# Rail_Protection_AD.net
KiCad netlist of a schematic drawn in Altium Designer
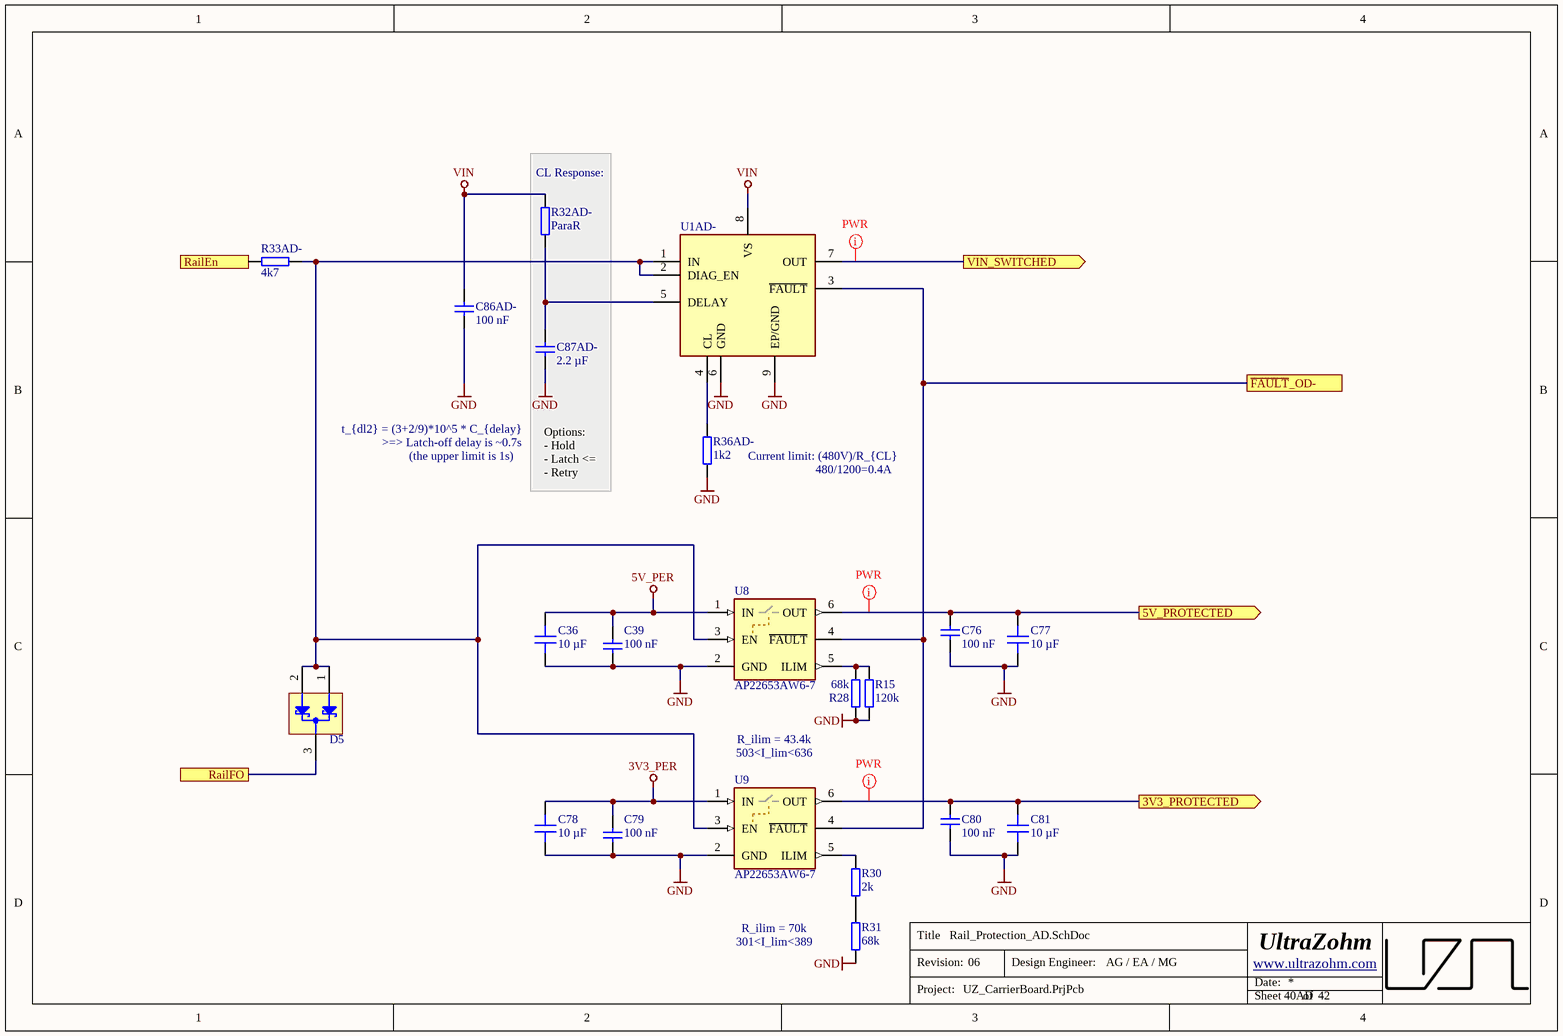
[diagram p0: Rail_Protection_AD.SchDoc]

(export (version "E")
  (design (tool "Eeschema 10.0.6"))
  (components
    (comp (ref "C36")
      (value "10 µF")
      (footprint "C_0603_TE")
      (description "Capacitor 0603, 16 VDC, 10 µF, X5R")
      (fields
        (field (name "MANUFACTURER PART NUMBER") "CL10A106MO8NQNC")
        (field (name "MANUFACTURER") "Samsung Electro-Mechanics")
        (field (name "CREATED FROM") "AGeiger")
      )
      (libsource (lib "user") (part "Capacitor"))
    )
    (comp (ref "C39")
      (value "100 nF")
      (footprint "C_0603_TE")
      (description "Generic capacitor")
      (fields
        (field (name "MANUFACTURER PART NUMBER") "UZgen_C_0603_100nF_50V_X7R")
        (field (name "MANUFACTURER") "UZgen")
        (field (name "CREATED FROM") "AGeiger")
      )
      (libsource (lib "user") (part "CAP-NP"))
    )
    (comp (ref "C76")
      (value "100 nF")
      (footprint "C_0603_TE")
      (description "Generic capacitor")
      (fields
        (field (name "MANUFACTURER PART NUMBER") "UZgen_C_0603_100nF_50V_X7R")
        (field (name "MANUFACTURER") "UZgen")
        (field (name "CREATED FROM") "AGeiger")
      )
      (libsource (lib "user") (part "CAP-NP"))
    )
    (comp (ref "C77")
      (value "10 µF")
      (footprint "C_0603_TE")
      (description "Capacitor 0603, 16 VDC, 10 µF, X5R")
      (fields
        (field (name "MANUFACTURER PART NUMBER") "CL10A106MO8NQNC")
        (field (name "MANUFACTURER") "Samsung Electro-Mechanics")
        (field (name "CREATED FROM") "AGeiger")
      )
      (libsource (lib "user") (part "Capacitor"))
    )
    (comp (ref "C78")
      (value "10 µF")
      (footprint "C_0603_TE")
      (description "Capacitor 0603, 16 VDC, 10 µF, X5R")
      (fields
        (field (name "MANUFACTURER PART NUMBER") "CL10A106MO8NQNC")
        (field (name "MANUFACTURER") "Samsung Electro-Mechanics")
        (field (name "CREATED FROM") "AGeiger")
      )
      (libsource (lib "user") (part "Capacitor"))
    )
    (comp (ref "C79")
      (value "100 nF")
      (footprint "C_0603_TE")
      (description "Generic capacitor")
      (fields
        (field (name "MANUFACTURER PART NUMBER") "UZgen_C_0603_100nF_50V_X7R")
        (field (name "MANUFACTURER") "UZgen")
        (field (name "CREATED FROM") "AGeiger")
      )
      (libsource (lib "user") (part "CAP-NP"))
    )
    (comp (ref "C80")
      (value "100 nF")
      (footprint "C_0603_TE")
      (description "Generic capacitor")
      (fields
        (field (name "MANUFACTURER PART NUMBER") "UZgen_C_0603_100nF_50V_X7R")
        (field (name "MANUFACTURER") "UZgen")
        (field (name "CREATED FROM") "AGeiger")
      )
      (libsource (lib "user") (part "CAP-NP"))
    )
    (comp (ref "C81")
      (value "10 µF")
      (footprint "C_0603_TE")
      (description "Capacitor 0603, 16 VDC, 10 µF, X5R")
      (fields
        (field (name "MANUFACTURER PART NUMBER") "CL10A106MO8NQNC")
        (field (name "MANUFACTURER") "Samsung Electro-Mechanics")
        (field (name "CREATED FROM") "AGeiger")
      )
      (libsource (lib "user") (part "Capacitor"))
    )
    (comp (ref "C86AD-")
      (value "100 nF")
      (footprint "C_0603_TE")
      (description "Generic capacitor")
      (fields
        (field (name "MANUFACTURER PART NUMBER") "UZgen_C_0603_100nF_50V_X7R")
        (field (name "MANUFACTURER") "UZgen")
        (field (name "CREATED FROM") "AGeiger")
      )
      (libsource (lib "user") (part "CAP-NP"))
    )
    (comp (ref "C87AD-")
      (value "2.2 µF")
      (footprint "C_0603_TE")
      (description "Generic capacitor")
      (fields
        (field (name "MANUFACTURER PART NUMBER") "UZgen_C_0603_2.2uF_50V_X7R")
        (field (name "MANUFACTURER") "UZgen")
        (field (name "CREATED FROM") "UZgenTool")
      )
      (libsource (lib "user") (part "CAP-NP"))
    )
    (comp (ref "D5")
      (value "BAT54CT-7-F")
      (footprint "SOT523-3")
      (description "Surface-mount Schottky Barrier Diode, 1 Pair Common Cathode 1V@100mA 200mA 2uA@25V 30V SOT-523-3")
      (fields
        (field (name "MANUFACTURER") "Diodes Incorporated")
        (field (name "LCSC PART NUMBER") "C134407")
        (field (name "CREATED FROM") "MGeier")
      )
      (libsource (lib "user") (part "DualCommonCathode3K"))
    )
    (comp (ref "R15")
      (value "120k")
      (footprint "R_0603_TE")
      (description "Generic resistor")
      (fields
        (field (name "MANUFACTURER PART NUMBER") "UZgen_R_0603_120k")
        (field (name "MANUFACTURER") "UZgen")
        (field (name "CREATED FROM") "UZgenTool")
      )
      (libsource (lib "user") (part "RES"))
    )
    (comp (ref "R28")
      (value "68k")
      (footprint "R_0603_TE")
      (description "Generic resistor")
      (fields
        (field (name "MANUFACTURER PART NUMBER") "UZgen_R_0603_68k")
        (field (name "MANUFACTURER") "UZgen")
        (field (name "CREATED FROM") "UZgenTool")
      )
      (libsource (lib "user") (part "RES"))
    )
    (comp (ref "R30")
      (value "2k")
      (footprint "R_0603_TE")
      (description "Generic resistor")
      (fields
        (field (name "MANUFACTURER PART NUMBER") "UZgen_R_0603_2k")
        (field (name "MANUFACTURER") "UZgen")
        (field (name "CREATED FROM") "UZgenTool")
      )
      (libsource (lib "user") (part "RES"))
    )
    (comp (ref "R31")
      (value "68k")
      (footprint "R_0603_TE")
      (description "Generic resistor")
      (fields
        (field (name "MANUFACTURER PART NUMBER") "UZgen_R_0603_68k")
        (field (name "MANUFACTURER") "UZgen")
        (field (name "CREATED FROM") "UZgenTool")
      )
      (libsource (lib "user") (part "RES"))
    )
    (comp (ref "R32AD-")
      (value "ParaR")
      (footprint "R_0603_TE")
      (description "Generic resistor (parametric)")
      (fields
        (field (name "MANUFACTURER PART NUMBER") "UZgen_R_0603_ParaR")
        (field (name "MANUFACTURER") "UZgen")
        (field (name "CREATED FROM") "UZgenTool")
      )
      (libsource (lib "user") (part "RES"))
    )
    (comp (ref "R33AD-")
      (value "4k7")
      (footprint "R_0603_TE")
      (description "Generic resistor")
      (fields
        (field (name "MANUFACTURER PART NUMBER") "UZgen_R_0603_4k7")
        (field (name "MANUFACTURER") "UZgen")
        (field (name "CREATED FROM") "UZgenTool")
      )
      (libsource (lib "user") (part "RES"))
    )
    (comp (ref "R36AD-")
      (value "1k2")
      (footprint "R_0603_TE")
      (description "Generic resistor")
      (fields
        (field (name "MANUFACTURER PART NUMBER") "UZgen_R_0603_1k2")
        (field (name "MANUFACTURER") "UZgen")
        (field (name "CREATED FROM") "UZgenTool")
      )
      (libsource (lib "user") (part "RES"))
    )
    (comp (ref "U1AD-")
      (value "TPS1H000AQDGNRQ1")
      (footprint "SOP65P490X110-9N")
      (fields
        (field (name "MANUFACTURER") "Texas Instruments")
        (field (name "LCSC PART NUMBER") "C2653764")
        (field (name "CREATED FROM") "FRosner")
      )
      (libsource (lib "user") (part "TPS1H000AQDGNRQ1"))
    )
    (comp (ref "U8")
      (value "AP22653AW6-7")
      (footprint "TSOT26-6")
      (description "Precision Adjustable Current-limited Power Switch")
      (fields
        (field (name "MANUFACTURER") "Diodes Incorporated")
        (field (name "LCSC PART NUMBER") "C1511768")
        (field (name "CREATED FROM") "MGeier")
      )
      (libsource (lib "user") (part "AP22653W6-7"))
    )
    (comp (ref "U9")
      (value "AP22653AW6-7")
      (footprint "TSOT26-6")
      (description "Precision Adjustable Current-limited Power Switch")
      (fields
        (field (name "MANUFACTURER") "Diodes Incorporated")
        (field (name "LCSC PART NUMBER") "C1511768")
        (field (name "CREATED FROM") "MGeier")
      )
      (libsource (lib "user") (part "AP22653W6-7"))
    )
  )
  (nets
    (net (code "1") (name "/3V3_PROTECTED") (class "Default")
      (node (ref "C80") (pin "1") (pinfunction "1_1") (pintype "passive"))
      (node (ref "C81") (pin "2") (pinfunction "2_2") (pintype "passive"))
      (node (ref "U9") (pin "6") (pinfunction "OUT_6") (pintype "output"))
    )
    (net (code "2") (name "/5V_PROTECTED") (class "Default")
      (node (ref "C76") (pin "1") (pinfunction "1_1") (pintype "passive"))
      (node (ref "C77") (pin "2") (pinfunction "2_2") (pintype "passive"))
      (node (ref "U8") (pin "6") (pinfunction "OUT_6") (pintype "output"))
    )
    (net (code "3") (name "/RailEn") (class "Default")
      (node (ref "R33AD-") (pin "1") (pinfunction "1_1") (pintype "passive"))
    )
    (net (code "4") (name "/RailFO") (class "Default")
      (node (ref "D5") (pin "3") (pinfunction "K_3") (pintype "passive"))
    )
    (net (code "5") (name "/VIN_SWITCHED") (class "Default")
      (node (ref "U1AD-") (pin "7") (pinfunction "OUT_7") (pintype "passive"))
    )
    (net (code "6") (name "/~{FAULT}_OD-") (class "Default")
      (node (ref "U1AD-") (pin "3") (pinfunction "~{FAULT}_3") (pintype "open_collector"))
      (node (ref "U8") (pin "4") (pinfunction "~{FAULT}_4") (pintype "open_collector"))
      (node (ref "U9") (pin "4") (pinfunction "~{FAULT}_4") (pintype "open_collector"))
    )
    (net (code "7") (name "3V3_PER") (class "Default")
      (node (ref "C78") (pin "2") (pinfunction "2_2") (pintype "passive"))
      (node (ref "C79") (pin "1") (pinfunction "1_1") (pintype "passive"))
      (node (ref "U9") (pin "1") (pinfunction "IN_1") (pintype "input"))
    )
    (net (code "8") (name "5V_PER") (class "Default")
      (node (ref "C36") (pin "2") (pinfunction "2_2") (pintype "passive"))
      (node (ref "C39") (pin "1") (pinfunction "1_1") (pintype "passive"))
      (node (ref "U8") (pin "1") (pinfunction "IN_1") (pintype "input"))
    )
    (net (code "9") (name "GND") (class "Default")
      (node (ref "C36") (pin "1") (pinfunction "1_1") (pintype "passive"))
      (node (ref "C39") (pin "2") (pinfunction "2_2") (pintype "passive"))
      (node (ref "C76") (pin "2") (pinfunction "2_2") (pintype "passive"))
      (node (ref "C77") (pin "1") (pinfunction "1_1") (pintype "passive"))
      (node (ref "C78") (pin "1") (pinfunction "1_1") (pintype "passive"))
      (node (ref "C79") (pin "2") (pinfunction "2_2") (pintype "passive"))
      (node (ref "C80") (pin "2") (pinfunction "2_2") (pintype "passive"))
      (node (ref "C81") (pin "1") (pinfunction "1_1") (pintype "passive"))
      (node (ref "C86AD-") (pin "1") (pinfunction "1_1") (pintype "passive"))
      (node (ref "C87AD-") (pin "1") (pinfunction "1_1") (pintype "passive"))
      (node (ref "R15") (pin "2") (pinfunction "2_2") (pintype "passive"))
      (node (ref "R28") (pin "2") (pinfunction "2_2") (pintype "passive"))
      (node (ref "R31") (pin "2") (pinfunction "2_2") (pintype "passive"))
      (node (ref "R36AD-") (pin "1") (pinfunction "1_1") (pintype "passive"))
      (node (ref "U1AD-") (pin "6") (pinfunction "GND_6") (pintype "passive"))
      (node (ref "U1AD-") (pin "9") (pinfunction "EP/GND_9") (pintype "passive"))
      (node (ref "U8") (pin "2") (pinfunction "GND_2") (pintype "power_in"))
      (node (ref "U9") (pin "2") (pinfunction "GND_2") (pintype "power_in"))
    )
    (net (code "10") (name "Net-(R30-Pad2)") (class "Default")
      (node (ref "R30") (pin "2") (pinfunction "2_2") (pintype "passive"))
      (node (ref "R31") (pin "1") (pinfunction "1_1") (pintype "passive"))
    )
    (net (code "11") (name "Net-(U1AD--CL)") (class "Default")
      (node (ref "R36AD-") (pin "2") (pinfunction "2_2") (pintype "passive"))
      (node (ref "U1AD-") (pin "4") (pinfunction "CL_4") (pintype "passive"))
    )
    (net (code "12") (name "Net-(U1AD--DELAY)") (class "Default")
      (node (ref "C87AD-") (pin "2") (pinfunction "2_2") (pintype "passive"))
      (node (ref "R32AD-") (pin "1") (pinfunction "1_1") (pintype "passive"))
      (node (ref "U1AD-") (pin "5") (pinfunction "DELAY_5") (pintype "passive"))
    )
    (net (code "13") (name "Net-(U1AD--DIAG_EN)") (class "Default")
      (node (ref "D5") (pin "1") (pinfunction "A_1") (pintype "passive"))
      (node (ref "D5") (pin "2") (pinfunction "A_2") (pintype "passive"))
      (node (ref "R33AD-") (pin "2") (pinfunction "2_2") (pintype "passive"))
      (node (ref "U1AD-") (pin "1") (pinfunction "IN_1") (pintype "passive"))
      (node (ref "U1AD-") (pin "2") (pinfunction "DIAG_EN_2") (pintype "passive"))
      (node (ref "U8") (pin "3") (pinfunction "EN_3") (pintype "input"))
      (node (ref "U9") (pin "3") (pinfunction "EN_3") (pintype "input"))
    )
    (net (code "14") (name "Net-(U8-ILIM)") (class "Default")
      (node (ref "R15") (pin "1") (pinfunction "1_1") (pintype "passive"))
      (node (ref "R28") (pin "1") (pinfunction "1_1") (pintype "passive"))
      (node (ref "U8") (pin "5") (pinfunction "ILIM_5") (pintype "output"))
    )
    (net (code "15") (name "Net-(U9-ILIM)") (class "Default")
      (node (ref "R30") (pin "1") (pinfunction "1_1") (pintype "passive"))
      (node (ref "U9") (pin "5") (pinfunction "ILIM_5") (pintype "output"))
    )
    (net (code "16") (name "VIN") (class "Default")
      (node (ref "C86AD-") (pin "2") (pinfunction "2_2") (pintype "passive"))
      (node (ref "R32AD-") (pin "2") (pinfunction "2_2") (pintype "passive"))
      (node (ref "U1AD-") (pin "8") (pinfunction "VS_8") (pintype "passive"))
    )
  )
)
